# SAMD21_Main_SCH.net
KiCad netlist of a schematic drawn in Altium Designer
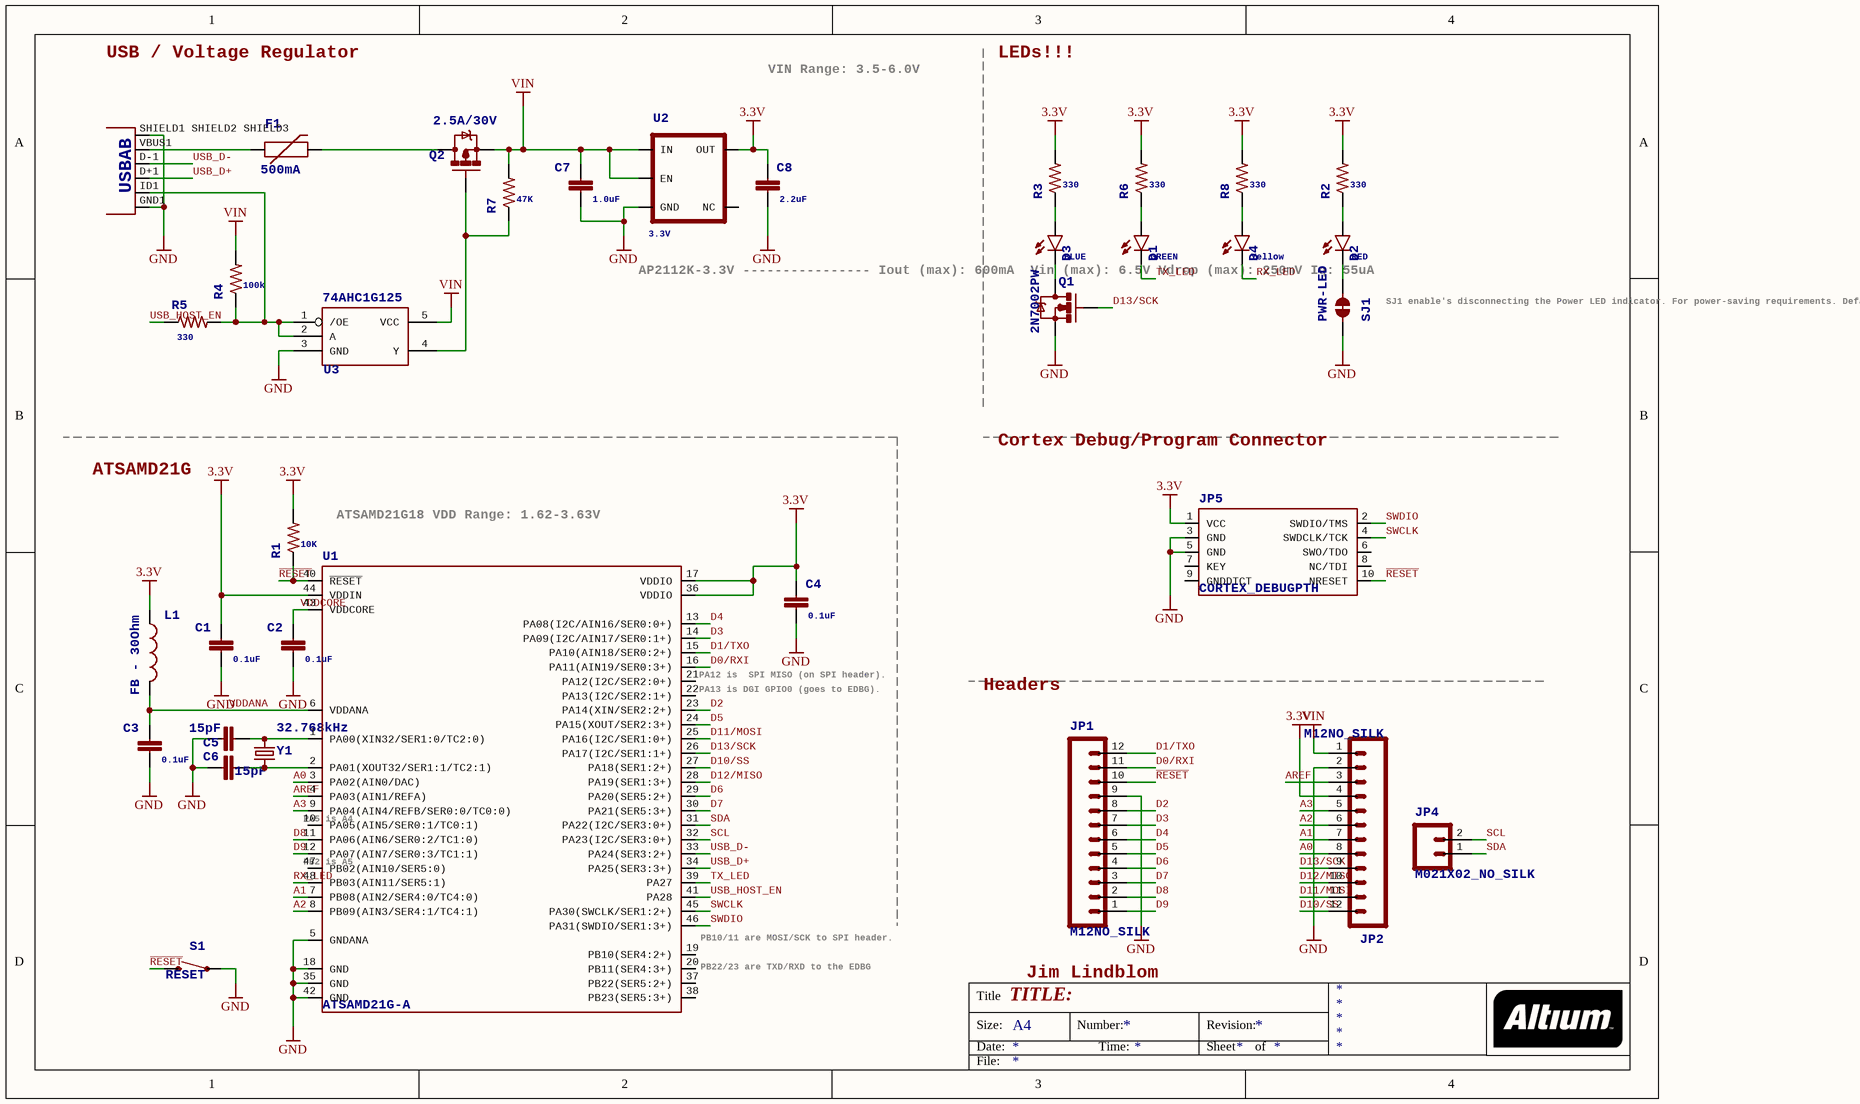
[diagram p0: SAMD21_Main_SCH.SchDoc]

(export (version "E")
  (design (tool "Eeschema 10.0.6"))
  (components
    (comp (ref "C1")
      (value "0.1uF")
      (footprint "0402-CAP")
      (fields (field (name ">NAME") "C1"))
      (libsource (lib "") (part "0.1UF-16V(+-10%)(0402)_1"))
    )
    (comp (ref "C2")
      (value "0.1uF")
      (footprint "0402-CAP")
      (fields (field (name ">NAME") "C2"))
      (libsource (lib "") (part "0.1UF-16V(+-10%)(0402)_1"))
    )
    (comp (ref "C3")
      (value "0.1uF")
      (footprint "0402-CAP")
      (fields (field (name ">NAME") "C3"))
      (libsource (lib "") (part "0.1UF-16V(+-10%)(0402)_1"))
    )
    (comp (ref "C4")
      (value "0.1uF")
      (footprint "0402-CAP")
      (fields (field (name ">NAME") "C4"))
      (libsource (lib "SparkFun-Capacitors") (part "0.1UF-16V(+-10%)(0402)"))
    )
    (comp (ref "C5")
      (value "15pF")
      (footprint "0402-CAP")
      (libsource (lib "") (part "15PF-50V(+-5%)(0402)_1"))
    )
    (comp (ref "C6")
      (value "15pF")
      (footprint "0402-CAP")
      (libsource (lib "samd21-temp") (part "15PF-50V(+-5%)(0402)"))
    )
    (comp (ref "C7")
      (value "1.0uF")
      (footprint "0805-CAP")
      (description "CAP-11625")
      (fields (field (name ">NAME") "C7"))
      (libsource (lib "SparkFun-Capacitors") (part "1.0UF-25V-+80/-20(0805){dblquote}"))
    )
    (comp (ref "C8")
      (value "2.2uF")
      (footprint "0603-CAP")
      (description "CAP-07888")
      (fields (field (name ">NAME") "C8"))
      (libsource (lib "SparkFun-Capacitors") (part "2.2UF-10V-20%(0603)"))
    )
    (comp (ref "D1")
      (value "GREEN")
      (footprint "LED-0603")
      (fields (field (name ">NAME") "D1"))
      (libsource (lib "SparkFun-LED") (part "LED-GREEN0603"))
    )
    (comp (ref "D2")
      (value "RED")
      (footprint "LED-0603")
      (fields (field (name ">NAME") "D2"))
      (libsource (lib "SparkFun-LED") (part "LED-RED0603"))
    )
    (comp (ref "D3")
      (value "BLUE")
      (footprint "LED-0603")
      (fields (field (name ">NAME") "D3"))
      (libsource (lib "SparkFun-LED") (part "LED-BLUE0603"))
    )
    (comp (ref "D4")
      (value "Yellow")
      (footprint "LED-0603")
      (fields (field (name ">NAME") "D4"))
      (libsource (lib "SparkFun-LED") (part "LED-YELLOW0603"))
    )
    (comp (ref "F1")
      (value "500mA")
      (footprint "PTC-1206")
      (description "<b>Resettable Fuse PTC</b>\nResettable Fuse. Spark Fun Electronics SKU : COM-08357")
      (fields (field (name ">NAME") "F1") (field (name ">VALUE") "500mA"))
      (libsource (lib "SparkFun-PowerIC") (part "PTCSMD"))
    )
    (comp (ref "JP1")
      (value "M12NO_SILK")
      (footprint "1X12_NO_SILK")
      (fields (field (name ">VALUE") "M12NO_SILK") (field (name ">NAME") "JP1"))
      (libsource (lib "SparkFun-Connectors") (part "M12NO_SILK"))
    )
    (comp (ref "JP2")
      (value "M12NO_SILK")
      (footprint "1X12_NO_SILK")
      (fields (field (name ">VALUE") "M12NO_SILK") (field (name ">NAME") "JP2"))
      (libsource (lib "SparkFun-Connectors") (part "M12NO_SILK"))
    )
    (comp (ref "JP3")
      (value "USB-ABCONN-11794")
      (footprint "USB-AB-MICRO-SMD_V03")
      (fields (field (name "USBAB") "USBAB"))
      (libsource (lib "SparkFun-Connectors") (part "USB-ABCONN-11794"))
    )
    (comp (ref "JP4")
      (value "M021X02_NO_SILK")
      (footprint "1X02_NO_SILK")
      (fields (field (name ">VALUE") "M021X02_NO_SILK") (field (name ">NAME") "JP4"))
      (libsource (lib "SparkFun-Connectors") (part "M021X02_NO_SILK"))
    )
    (comp (ref "JP5")
      (value "CORTEX_DEBUGPTH")
      (footprint "2X5-PTH-1.27MM")
      (fields (field (name ">NAME") "JP5") (field (name ">VALUE") "CORTEX_DEBUGPTH"))
      (libsource (lib "samd21-temp") (part "CORTEX_DEBUGPTH"))
    )
    (comp (ref "L1")
      (value "FB - 30Ohm")
      (footprint "0603")
      (libsource (lib "SparkFun-Passives") (part "INDUCTOR0603"))
    )
    (comp (ref "Q1")
      (value "2N7002PW")
      (footprint "SOT323")
      (libsource (lib "SparkFun-DiscreteSemi") (part "MOSFET-NCHANNEL2N7002PW"))
    )
    (comp (ref "Q2")
      (value "2.5A/30V")
      (footprint "SOT23-3")
      (libsource (lib "SparkFun-DiscreteSemi") (part "MOSFET-PCHANNELDMG2307L"))
    )
    (comp (ref "R1")
      (value "10K")
      (footprint "0603-RES")
      (description "RES-00824")
      (fields (field (name ">NAME") "R1"))
      (libsource (lib "SparkFun-Resistors") (part "10KOHM-1/10W-1%(0603)0603"))
    )
    (comp (ref "R2")
      (value "330")
      (footprint "0603-RES")
      (description "RES-00818")
      (fields (field (name ">NAME") "R2"))
      (libsource (lib "SparkFun-Resistors") (part "330OHM1/10W1%(0603)"))
    )
    (comp (ref "R3")
      (value "330")
      (footprint "0603-RES")
      (description "RES-00818")
      (fields (field (name ">NAME") "R3"))
      (libsource (lib "SparkFun-Resistors") (part "330OHM1/10W1%(0603)"))
    )
    (comp (ref "R4")
      (value "100k")
      (footprint "0603-RES")
      (description "RES-07828")
      (fields (field (name ">NAME") "R4"))
      (libsource (lib "SparkFun-Resistors") (part "100KOHM-1/10W-1%(0603)"))
    )
    (comp (ref "R5")
      (value "330")
      (footprint "0603-RES")
      (description "RES-00818")
      (fields (field (name ">NAME") "R5"))
      (libsource (lib "SparkFun-Resistors") (part "330OHM1/10W1%(0603)"))
    )
    (comp (ref "R6")
      (value "330")
      (footprint "0603-RES")
      (description "RES-00818")
      (fields (field (name ">NAME") "R6"))
      (libsource (lib "SparkFun-Resistors") (part "330OHM1/10W1%(0603)"))
    )
    (comp (ref "R7")
      (value "47K")
      (footprint "0603-RES")
      (description "RES-07871")
      (fields (field (name ">NAME") "R7"))
      (libsource (lib "SparkFun-Resistors") (part "47KOHM1/10W1%(0603)"))
    )
    (comp (ref "R8")
      (value "330")
      (footprint "0603-RES")
      (description "RES-00818")
      (fields (field (name ">NAME") "R8"))
      (libsource (lib "SparkFun-Resistors") (part "330OHM1/10W1%(0603)"))
    )
    (comp (ref "S1")
      (value "RESET")
      (footprint "TACTILE_SWITCH_SMD_4.6X2.8MM")
      (description "Various NO switches- pushbuttons, reed, etc")
      (fields (field (name ">NAME") "S1") (field (name ">VALUE") "RESET"))
      (libsource (lib "samd21-temp") (part "SWITCH-MOMENTARY-2SMD-4.6X2.8MM"))
    )
    (comp (ref "SJ1")
      (value "PWR-LED")
      (footprint "PAD-JUMPER-2-NC_BY_TRACE_NO_SILK")
      (fields (field (name ">NAME") "SJ1") (field (name ">VALUE") "PWR-LED"))
      (libsource (lib "SparkFun-Passives") (part "JUMPER-PAD-2-NC_BY_TRACENO_SILK"))
    )
    (comp (ref "U1")
      (value "ATSAMD21G-A")
      (footprint "TQFP-48")
      (fields (field (name ">NAME") "U1") (field (name ">VALUE") "ATSAMD21G-A"))
      (libsource (lib "samd21-temp") (part "ATSAMD21G-A"))
    )
    (comp (ref "U2")
      (value "3.3V")
      (footprint "SOT23-5")
      (fields (field (name ">NAME") "U2"))
      (libsource (lib "SparkFun-PowerIC") (part "V_REG_AP2112K-3.3V"))
    )
    (comp (ref "U3")
      (value "74AHC1G125")
      (footprint "SOT23-5")
      (description "Single bus buffer gate with 3-state output")
      (fields (field (name ">VALUE") "74AHC1G125") (field (name ">NAME") "U3"))
      (libsource (lib "SparkFun-DigitalIC") (part "74AHC1G125"))
    )
    (comp (ref "Y1")
      (value "32.768kHz")
      (footprint "CRYSTAL-SMD-3.2X1.5MM")
      (description "Various standard crystals. Proven footprints.")
      (libsource (lib "samd21-temp") (part "CRYSTAL3.2X1.5MM"))
    )
  )
  (nets
    (net (code "1") (name "/A0") (class "Default")
      (node (ref "JP2") (pin "8") (pinfunction "8_8") (pintype "passive"))
      (node (ref "U1") (pin "3") (pinfunction "PA02(AIN0/DAC)_3") (pintype "passive"))
    )
    (net (code "2") (name "/A1") (class "Default")
      (node (ref "JP2") (pin "7") (pinfunction "7_7") (pintype "passive"))
      (node (ref "U1") (pin "7") (pinfunction "PB08(AIN2/SER4:0/TC4:0)_7") (pintype "passive"))
    )
    (net (code "3") (name "/A2") (class "Default")
      (node (ref "JP2") (pin "6") (pinfunction "6_6") (pintype "passive"))
      (node (ref "U1") (pin "8") (pinfunction "PB09(AIN3/SER4:1/TC4:1)_8") (pintype "passive"))
    )
    (net (code "4") (name "/A3") (class "Default")
      (node (ref "JP2") (pin "5") (pinfunction "5_5") (pintype "passive"))
      (node (ref "U1") (pin "9") (pinfunction "PA04(AIN4/REFB/SER0:0/TC0:0)_9") (pintype "passive"))
    )
    (net (code "5") (name "/AREF") (class "Default")
      (node (ref "JP2") (pin "3") (pinfunction "3_3") (pintype "passive"))
      (node (ref "U1") (pin "4") (pinfunction "PA03(AIN1/REFA)_4") (pintype "passive"))
    )
    (net (code "6") (name "/D0{slash}RXI") (class "Default")
      (node (ref "JP1") (pin "11") (pinfunction "11_11") (pintype "passive"))
      (node (ref "U1") (pin "16") (pinfunction "PA11(AIN19/SER0:3+)_16") (pintype "passive"))
    )
    (net (code "7") (name "/D1{slash}TXO") (class "Default")
      (node (ref "JP1") (pin "12") (pinfunction "12_12") (pintype "passive"))
      (node (ref "U1") (pin "15") (pinfunction "PA10(AIN18/SER0:2+)_15") (pintype "passive"))
    )
    (net (code "8") (name "/D2") (class "Default")
      (node (ref "JP1") (pin "8") (pinfunction "8_8") (pintype "passive"))
      (node (ref "U1") (pin "23") (pinfunction "PA14(XIN/SER2:2+)_23") (pintype "passive"))
    )
    (net (code "9") (name "/D3") (class "Default")
      (node (ref "JP1") (pin "7") (pinfunction "7_7") (pintype "passive"))
      (node (ref "U1") (pin "14") (pinfunction "PA09(I2C/AIN17/SER0:1+)_14") (pintype "passive"))
    )
    (net (code "10") (name "/D4") (class "Default")
      (node (ref "JP1") (pin "6") (pinfunction "6_6") (pintype "passive"))
      (node (ref "U1") (pin "13") (pinfunction "PA08(I2C/AIN16/SER0:0+)_13") (pintype "passive"))
    )
    (net (code "11") (name "/D5") (class "Default")
      (node (ref "JP1") (pin "5") (pinfunction "5_5") (pintype "passive"))
      (node (ref "U1") (pin "24") (pinfunction "PA15(XOUT/SER2:3+)_24") (pintype "passive"))
    )
    (net (code "12") (name "/D6") (class "Default")
      (node (ref "JP1") (pin "4") (pinfunction "4_4") (pintype "passive"))
      (node (ref "U1") (pin "29") (pinfunction "PA20(SER5:2+)_29") (pintype "passive"))
    )
    (net (code "13") (name "/D7") (class "Default")
      (node (ref "JP1") (pin "3") (pinfunction "3_3") (pintype "passive"))
      (node (ref "U1") (pin "30") (pinfunction "PA21(SER5:3+)_30") (pintype "passive"))
    )
    (net (code "14") (name "/D8") (class "Default")
      (node (ref "JP1") (pin "2") (pinfunction "2_2") (pintype "passive"))
      (node (ref "U1") (pin "11") (pinfunction "PA06(AIN6/SER0:2/TC1:0)_11") (pintype "passive"))
    )
    (net (code "15") (name "/D9") (class "Default")
      (node (ref "JP1") (pin "1") (pinfunction "1_1") (pintype "passive"))
      (node (ref "U1") (pin "12") (pinfunction "PA07(AIN7/SER0:3/TC1:1)_12") (pintype "passive"))
    )
    (net (code "16") (name "/D10{slash}SS") (class "Default")
      (node (ref "JP2") (pin "12") (pinfunction "12_12") (pintype "passive"))
      (node (ref "U1") (pin "27") (pinfunction "PA18(SER1:2+)_27") (pintype "passive"))
    )
    (net (code "17") (name "/D11{slash}MOSI") (class "Default")
      (node (ref "JP2") (pin "11") (pinfunction "11_11") (pintype "passive"))
      (node (ref "U1") (pin "25") (pinfunction "PA16(I2C/SER1:0+)_25") (pintype "passive"))
    )
    (net (code "18") (name "/D12{slash}MISO") (class "Default")
      (node (ref "JP2") (pin "10") (pinfunction "10_10") (pintype "passive"))
      (node (ref "U1") (pin "28") (pinfunction "PA19(SER1:3+)_28") (pintype "passive"))
    )
    (net (code "19") (name "/D13{slash}SCK") (class "Default")
      (node (ref "JP2") (pin "9") (pinfunction "9_9") (pintype "passive"))
      (node (ref "Q1") (pin "1") (pinfunction "G_1") (pintype "passive"))
      (node (ref "U1") (pin "26") (pinfunction "PA17(I2C/SER1:1+)_26") (pintype "passive"))
    )
    (net (code "20") (name "/RX_LED") (class "Default")
      (node (ref "D4") (pin "C") (pinfunction "C_C") (pintype "passive"))
      (node (ref "U1") (pin "48") (pinfunction "PB03(AIN11/SER5:1)_48") (pintype "passive"))
    )
    (net (code "21") (name "/SCL") (class "Default")
      (node (ref "JP4") (pin "2") (pinfunction "2_2") (pintype "passive"))
      (node (ref "U1") (pin "32") (pinfunction "PA23(I2C/SER3:0+)_32") (pintype "passive"))
    )
    (net (code "22") (name "/SDA") (class "Default")
      (node (ref "JP4") (pin "1") (pinfunction "1_1") (pintype "passive"))
      (node (ref "U1") (pin "31") (pinfunction "PA22(I2C/SER3:0+)_31") (pintype "passive"))
    )
    (net (code "23") (name "/SWCLK") (class "Default")
      (node (ref "JP5") (pin "4") (pinfunction "SWDCLK/TCK_4") (pintype "passive"))
      (node (ref "U1") (pin "45") (pinfunction "PA30(SWCLK/SER1:2+)_45") (pintype "passive"))
    )
    (net (code "24") (name "/SWDIO") (class "Default")
      (node (ref "JP5") (pin "2") (pinfunction "SWDIO/TMS_2") (pintype "passive"))
      (node (ref "U1") (pin "46") (pinfunction "PA31(SWDIO/SER1:3+)_46") (pintype "passive"))
    )
    (net (code "25") (name "/TX_LED") (class "Default")
      (node (ref "D1") (pin "C") (pinfunction "C_C") (pintype "passive"))
      (node (ref "U1") (pin "39") (pinfunction "PA27_39") (pintype "passive"))
    )
    (net (code "26") (name "/USB_D+") (class "Default")
      (node (ref "JP3") (pin "D+1") (pinfunction "D+_D+1") (pintype "passive"))
      (node (ref "U1") (pin "34") (pinfunction "PA25(SER3:3+)_34") (pintype "passive"))
    )
    (net (code "27") (name "/USB_D-") (class "Default")
      (node (ref "JP3") (pin "D-1") (pinfunction "D-_D-1") (pintype "passive"))
      (node (ref "U1") (pin "33") (pinfunction "PA24(SER3:2+)_33") (pintype "passive"))
    )
    (net (code "28") (name "/USB_HOST_EN") (class "Default")
      (node (ref "R5") (pin "1") (pinfunction "1_1") (pintype "passive"))
      (node (ref "U1") (pin "41") (pinfunction "PA28_41") (pintype "passive"))
    )
    (net (code "29") (name "/VDDANA") (class "Default")
      (node (ref "C3") (pin "1") (pinfunction "1_1") (pintype "passive"))
      (node (ref "L1") (pin "2") (pinfunction "2_2") (pintype "passive"))
      (node (ref "U1") (pin "6") (pinfunction "VDDANA_6") (pintype "passive"))
    )
    (net (code "30") (name "/VDDCORE") (class "Default")
      (node (ref "C2") (pin "1") (pinfunction "1_1") (pintype "passive"))
      (node (ref "U1") (pin "43") (pinfunction "VDDCORE_43") (pintype "passive"))
    )
    (net (code "31") (name "/~{RESET}") (class "Default")
      (node (ref "JP1") (pin "10") (pinfunction "10_10") (pintype "passive"))
      (node (ref "JP5") (pin "10") (pinfunction "NRESET_10") (pintype "passive"))
      (node (ref "R1") (pin "1") (pinfunction "1_1") (pintype "passive"))
      (node (ref "S1") (pin "3_4") (pinfunction "2_3_4") (pintype "passive"))
      (node (ref "U1") (pin "40") (pinfunction "~{RESET}_40") (pintype "passive"))
    )
    (net (code "32") (name "3.3V") (class "Default")
      (node (ref "C1") (pin "1") (pinfunction "1_1") (pintype "passive"))
      (node (ref "C4") (pin "1") (pinfunction "1_1") (pintype "passive"))
      (node (ref "C8") (pin "1") (pinfunction "1_1") (pintype "passive"))
      (node (ref "JP2") (pin "4") (pinfunction "4_4") (pintype "passive"))
      (node (ref "JP5") (pin "1") (pinfunction "VCC_1") (pintype "passive"))
      (node (ref "L1") (pin "1") (pinfunction "1_1") (pintype "passive"))
      (node (ref "R1") (pin "2") (pinfunction "2_2") (pintype "passive"))
      (node (ref "R2") (pin "2") (pinfunction "2_2") (pintype "passive"))
      (node (ref "R3") (pin "2") (pinfunction "2_2") (pintype "passive"))
      (node (ref "R6") (pin "2") (pinfunction "2_2") (pintype "passive"))
      (node (ref "R8") (pin "2") (pinfunction "2_2") (pintype "passive"))
      (node (ref "U1") (pin "17") (pinfunction "VDDIO_17") (pintype "passive"))
      (node (ref "U1") (pin "36") (pinfunction "VDDIO_36") (pintype "passive"))
      (node (ref "U1") (pin "44") (pinfunction "VDDIN_44") (pintype "passive"))
      (node (ref "U2") (pin "5") (pinfunction "OUT_5") (pintype "passive"))
    )
    (net (code "33") (name "GND") (class "Default")
      (node (ref "C1") (pin "2") (pinfunction "2_2") (pintype "passive"))
      (node (ref "C2") (pin "2") (pinfunction "2_2") (pintype "passive"))
      (node (ref "C3") (pin "2") (pinfunction "2_2") (pintype "passive"))
      (node (ref "C4") (pin "2") (pinfunction "2_2") (pintype "passive"))
      (node (ref "C5") (pin "1") (pinfunction "1_1") (pintype "passive"))
      (node (ref "C6") (pin "2") (pinfunction "2_2") (pintype "passive"))
      (node (ref "C7") (pin "2") (pinfunction "2_2") (pintype "passive"))
      (node (ref "C8") (pin "2") (pinfunction "2_2") (pintype "passive"))
      (node (ref "JP1") (pin "9") (pinfunction "9_9") (pintype "passive"))
      (node (ref "JP2") (pin "2") (pinfunction "2_2") (pintype "passive"))
      (node (ref "JP3") (pin "GND1") (pinfunction "GND_GND1") (pintype "passive"))
      (node (ref "JP3") (pin "SHIELD1_SHIELD2_SHIELD3") (pinfunction "SHIELD_SHIELD1_SHIELD2_SHIELD3") (pintype "passive"))
      (node (ref "JP5") (pin "3") (pinfunction "GND_3") (pintype "passive"))
      (node (ref "JP5") (pin "5") (pinfunction "GND_5") (pintype "passive"))
      (node (ref "Q1") (pin "2") (pinfunction "S_2") (pintype "passive"))
      (node (ref "S1") (pin "1_2") (pinfunction "1_1_2") (pintype "passive"))
      (node (ref "SJ1") (pin "1") (pinfunction "1_1") (pintype "passive"))
      (node (ref "U1") (pin "18") (pinfunction "GND_18") (pintype "passive"))
      (node (ref "U1") (pin "35") (pinfunction "GND_35") (pintype "passive"))
      (node (ref "U1") (pin "42") (pinfunction "GND_42") (pintype "passive"))
      (node (ref "U1") (pin "5") (pinfunction "GNDANA_5") (pintype "passive"))
      (node (ref "U2") (pin "2") (pinfunction "GND_2") (pintype "passive"))
      (node (ref "U3") (pin "3") (pinfunction "GND_3") (pintype "passive"))
    )
    (net (code "34") (name "Net-(D1-PadA)") (class "Default")
      (node (ref "D1") (pin "A") (pinfunction "A_A") (pintype "passive"))
      (node (ref "R6") (pin "1") (pinfunction "1_1") (pintype "passive"))
    )
    (net (code "35") (name "Net-(D2-PadA)") (class "Default")
      (node (ref "D2") (pin "A") (pinfunction "A_A") (pintype "passive"))
      (node (ref "R2") (pin "1") (pinfunction "1_1") (pintype "passive"))
    )
    (net (code "36") (name "Net-(D2-PadC)") (class "Default")
      (node (ref "D2") (pin "C") (pinfunction "C_C") (pintype "passive"))
      (node (ref "SJ1") (pin "2") (pinfunction "2_2") (pintype "passive"))
    )
    (net (code "37") (name "Net-(D3-PadA)") (class "Default")
      (node (ref "D3") (pin "A") (pinfunction "A_A") (pintype "passive"))
      (node (ref "R3") (pin "1") (pinfunction "1_1") (pintype "passive"))
    )
    (net (code "38") (name "Net-(D4-PadA)") (class "Default")
      (node (ref "D4") (pin "A") (pinfunction "A_A") (pintype "passive"))
      (node (ref "R8") (pin "1") (pinfunction "1_1") (pintype "passive"))
    )
    (net (code "39") (name "Net-(JP3-USBID)") (class "Default")
      (node (ref "JP3") (pin "ID1") (pinfunction "USBID_ID1") (pintype "passive"))
      (node (ref "R4") (pin "1") (pinfunction "1_1") (pintype "passive"))
      (node (ref "R5") (pin "2") (pinfunction "2_2") (pintype "passive"))
      (node (ref "U3") (pin "1") (pinfunction "/OE_1") (pintype "passive"))
      (node (ref "U3") (pin "2") (pinfunction "A_2") (pintype "passive"))
    )
    (net (code "40") (name "Net-(JP3-VBUS)") (class "Default")
      (node (ref "F1") (pin "1") (pinfunction "1_1") (pintype "passive"))
      (node (ref "JP3") (pin "VBUS1") (pinfunction "VBUS_VBUS1") (pintype "passive"))
    )
    (net (code "41") (name "Net-(Q1-D)") (class "Default")
      (node (ref "D3") (pin "C") (pinfunction "C_C") (pintype "passive"))
      (node (ref "Q1") (pin "3") (pinfunction "D_3") (pintype "passive"))
    )
    (net (code "42") (name "Net-(Q2-D)") (class "Default")
      (node (ref "F1") (pin "2") (pinfunction "2_2") (pintype "passive"))
      (node (ref "Q2") (pin "3") (pinfunction "D_3") (pintype "passive"))
    )
    (net (code "43") (name "Net-(Q2-G)") (class "Default")
      (node (ref "Q2") (pin "1") (pinfunction "G_1") (pintype "passive"))
      (node (ref "R7") (pin "1") (pinfunction "1_1") (pintype "passive"))
      (node (ref "U3") (pin "4") (pinfunction "Y_4") (pintype "passive"))
    )
    (net (code "44") (name "Net-(U1-PA00(XIN32{slash}SER1:0{slash}TC2:0))") (class "Default")
      (node (ref "C5") (pin "2") (pinfunction "2_2") (pintype "passive"))
      (node (ref "U1") (pin "1") (pinfunction "PA00(XIN32/SER1:0/TC2:0)_1") (pintype "passive"))
      (node (ref "Y1") (pin "P$2") (pinfunction "2_P$2") (pintype "passive"))
    )
    (net (code "45") (name "Net-(U1-PA01(XOUT32{slash}SER1:1{slash}TC2:1))") (class "Default")
      (node (ref "C6") (pin "1") (pinfunction "1_1") (pintype "passive"))
      (node (ref "U1") (pin "2") (pinfunction "PA01(XOUT32/SER1:1/TC2:1)_2") (pintype "passive"))
      (node (ref "Y1") (pin "P$1") (pinfunction "1_P$1") (pintype "passive"))
    )
    (net (code "46") (name "VIN") (class "Default")
      (node (ref "C7") (pin "1") (pinfunction "1_1") (pintype "passive"))
      (node (ref "JP2") (pin "1") (pinfunction "1_1") (pintype "passive"))
      (node (ref "Q2") (pin "2") (pinfunction "S_2") (pintype "passive"))
      (node (ref "R4") (pin "2") (pinfunction "2_2") (pintype "passive"))
      (node (ref "R7") (pin "2") (pinfunction "2_2") (pintype "passive"))
      (node (ref "U2") (pin "1") (pinfunction "IN_1") (pintype "passive"))
      (node (ref "U2") (pin "3") (pinfunction "EN_3") (pintype "passive"))
      (node (ref "U3") (pin "5") (pinfunction "VCC_5") (pintype "passive"))
    )
    (net (code "47") (name "unconnected-(JP5-GNDDTCT-Pad9)") (class "Default")
      (node (ref "JP5") (pin "9") (pinfunction "GNDDTCT_9") (pintype "passive"))
    )
    (net (code "48") (name "unconnected-(JP5-KEY-Pad7)") (class "Default")
      (node (ref "JP5") (pin "7") (pinfunction "KEY_7") (pintype "passive"))
    )
    (net (code "49") (name "unconnected-(JP5-NC{slash}TDI-Pad8)") (class "Default")
      (node (ref "JP5") (pin "8") (pinfunction "NC/TDI_8") (pintype "passive"))
    )
    (net (code "50") (name "unconnected-(JP5-SWO{slash}TDO-Pad6)") (class "Default")
      (node (ref "JP5") (pin "6") (pinfunction "SWO/TDO_6") (pintype "passive"))
    )
    (net (code "51") (name "unconnected-(U1-PA05(AIN5{slash}SER0:1{slash}TC0:1)-Pad10)") (class "Default")
      (node (ref "U1") (pin "10") (pinfunction "PA05(AIN5/SER0:1/TC0:1)_10") (pintype "passive"))
    )
    (net (code "52") (name "unconnected-(U1-PA12(I2C{slash}SER2:0+)-Pad21)") (class "Default")
      (node (ref "U1") (pin "21") (pinfunction "PA12(I2C/SER2:0+)_21") (pintype "passive"))
    )
    (net (code "53") (name "unconnected-(U1-PA13(I2C{slash}SER2:1+)-Pad22)") (class "Default")
      (node (ref "U1") (pin "22") (pinfunction "PA13(I2C/SER2:1+)_22") (pintype "passive"))
    )
    (net (code "54") (name "unconnected-(U1-PB02(AIN10{slash}SER5:0)-Pad47)") (class "Default")
      (node (ref "U1") (pin "47") (pinfunction "PB02(AIN10/SER5:0)_47") (pintype "passive"))
    )
    (net (code "55") (name "unconnected-(U1-PB10(SER4:2+)-Pad19)") (class "Default")
      (node (ref "U1") (pin "19") (pinfunction "PB10(SER4:2+)_19") (pintype "passive"))
    )
    (net (code "56") (name "unconnected-(U1-PB11(SER4:3+)-Pad20)") (class "Default")
      (node (ref "U1") (pin "20") (pinfunction "PB11(SER4:3+)_20") (pintype "passive"))
    )
    (net (code "57") (name "unconnected-(U1-PB22(SER5:2+)-Pad37)") (class "Default")
      (node (ref "U1") (pin "37") (pinfunction "PB22(SER5:2+)_37") (pintype "passive"))
    )
    (net (code "58") (name "unconnected-(U1-PB23(SER5:3+)-Pad38)") (class "Default")
      (node (ref "U1") (pin "38") (pinfunction "PB23(SER5:3+)_38") (pintype "passive"))
    )
    (net (code "59") (name "unconnected-(U2-NC-Pad4)") (class "Default")
      (node (ref "U2") (pin "4") (pinfunction "NC_4") (pintype "passive"))
    )
  )
)
